# SCH006.net
KiCad netlist of a schematic drawn in Altium Designer
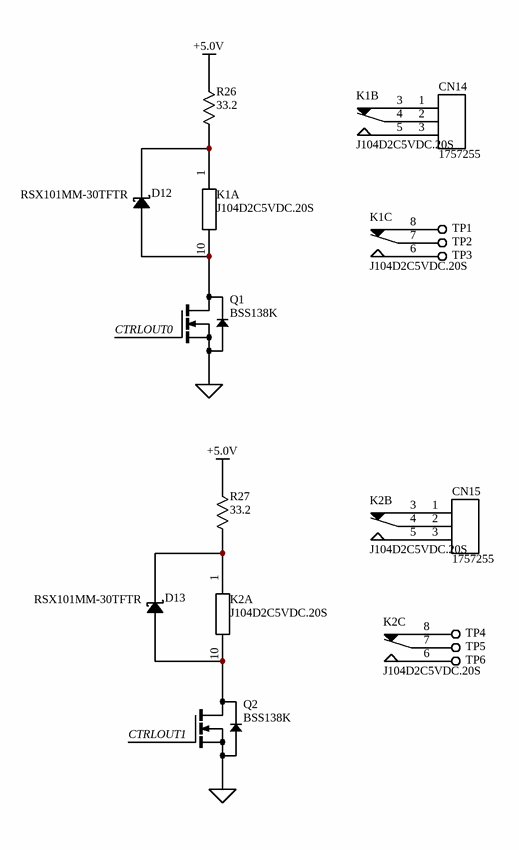
[diagram p0: SCH006.SchDoc]

(export (version "E")
  (design (tool "Eeschema 10.0.6"))
  (components
    (comp (ref "CN14")
      (value "1757255")
      (footprint "PHOENIX_1757255")
      (description "MSTBA 2,5/3-G-5,08 Pluggable Terminal Block 3 Pos 5.08mm pitch Through Hole Header")
      (fields (field (name "MANUFACTURER") "Phoenix Contact"))
      (libsource (lib "EM411-202401-RMC001-001") (part "1757255"))
    )
    (comp (ref "CN15")
      (value "1757255")
      (footprint "PHOENIX_1757255")
      (description "MSTBA 2,5/3-G-5,08 Pluggable Terminal Block 3 Pos 5.08mm pitch Through Hole Header")
      (fields (field (name "MANUFACTURER") "Phoenix Contact"))
      (libsource (lib "EM411-202401-RMC001-001") (part "1757255"))
    )
    (comp (ref "D12")
      (value "RSX101MM-30TFTR")
      (footprint "SODFL350X90-2N")
      (description "Schottky Barrier Diode")
      (fields (field (name "MANUFACTURER") "Rohm Semiconductor"))
      (libsource (lib "EM411-202401-RMC001-001") (part "RSX101MM-30TFTR"))
    )
    (comp (ref "D13")
      (value "RSX101MM-30TFTR")
      (footprint "SODFL350X90-2N")
      (description "Schottky Barrier Diode")
      (fields (field (name "MANUFACTURER") "Rohm Semiconductor"))
      (libsource (lib "EM411-202401-RMC001-001") (part "RSX101MM-30TFTR"))
    )
    (comp (ref "K1")
      (value "J104D2C5VDC.20S")
      (footprint "CIT_J104D")
      (description "J104D Series Dual Form C 5V, 2A PCB Relay")
      (fields (field (name "MANUFACTURER") "Circuit Interrupter Technology"))
      (libsource (lib "") (part "J104D2C5VDC.20S_1"))
    )
    (comp (ref "K2")
      (value "J104D2C5VDC.20S")
      (footprint "CIT_J104D")
      (description "J104D Series Dual Form C 5V, 2A PCB Relay")
      (fields (field (name "MANUFACTURER") "Circuit Interrupter Technology"))
      (libsource (lib "") (part "J104D2C5VDC.20S_1"))
    )
    (comp (ref "Q1")
      (value "BSS138K")
      (footprint "SOT95P237X111-3N")
      (description "N-Channel Logic Level Enhancement Mode Field Effect Transistor")
      (fields (field (name "MANUFACTURER") "Onsemi"))
      (libsource (lib "EM411-202401-RMC001-000-20240213-T10") (part "BSS138K"))
    )
    (comp (ref "Q2")
      (value "BSS138K")
      (footprint "SOT95P237X111-3N")
      (description "N-Channel Logic Level Enhancement Mode Field Effect Transistor")
      (fields (field (name "MANUFACTURER") "Onsemi"))
      (libsource (lib "EM411-202401-RMC001-000-20240213-T10") (part "BSS138K"))
    )
    (comp (ref "R26")
      (value "33.2")
      (footprint "RESC2012X06N")
      (description "33.2, 1%, 0.125W Thick Film Chip Resistor")
      (fields (field (name "MANUFACTURER") "Bourns") (field (name "PARTNUMBER") "CR0805-FX-33R2ELF"))
      (libsource (lib "EM411-202401-RMC001-001") (part "CR0805-FX-33R2ELF"))
    )
    (comp (ref "R27")
      (value "33.2")
      (footprint "RESC2012X06N")
      (description "33.2, 1%, 0.125W Thick Film Chip Resistor")
      (fields (field (name "MANUFACTURER") "Bourns") (field (name "PARTNUMBER") "CR0805-FX-33R2ELF"))
      (libsource (lib "EM411-202401-RMC001-001") (part "CR0805-FX-33R2ELF"))
    )
    (comp (ref "TP1")
      (value "Test Point")
      (footprint "TP100")
      (description "Test Point, Surface Mount, 3 mm")
      (fields (field (name "MANUFACTURER") "Confederation College"))
      (libsource (lib "EM411-202401-RMC001-001") (part "TP3"))
    )
    (comp (ref "TP2")
      (value "Test Point")
      (footprint "TP100")
      (description "Test Point, Surface Mount, 3 mm")
      (fields (field (name "MANUFACTURER") "Confederation College"))
      (libsource (lib "EM411-202401-RMC001-001") (part "TP3"))
    )
    (comp (ref "TP3")
      (value "Test Point")
      (footprint "TP100")
      (description "Test Point, Surface Mount, 3 mm")
      (fields (field (name "MANUFACTURER") "Confederation College"))
      (libsource (lib "EM411-202401-RMC001-001") (part "TP3"))
    )
    (comp (ref "TP4")
      (value "Test Point")
      (footprint "TP100")
      (description "Test Point, Surface Mount, 3 mm")
      (fields (field (name "MANUFACTURER") "Confederation College"))
      (libsource (lib "EM411-202401-RMC001-001") (part "TP3"))
    )
    (comp (ref "TP5")
      (value "Test Point")
      (footprint "TP100")
      (description "Test Point, Surface Mount, 3 mm")
      (fields (field (name "MANUFACTURER") "Confederation College"))
      (libsource (lib "EM411-202401-RMC001-001") (part "TP3"))
    )
    (comp (ref "TP6")
      (value "Test Point")
      (footprint "TP100")
      (description "Test Point, Surface Mount, 3 mm")
      (fields (field (name "MANUFACTURER") "Confederation College"))
      (libsource (lib "EM411-202401-RMC001-001") (part "TP3"))
    )
  )
  (nets
    (net (code "1") (name "+5.0V") (class "Default")
      (node (ref "R26") (pin "2") (pinfunction "2_2") (pintype "passive"))
      (node (ref "R27") (pin "2") (pinfunction "2_2") (pintype "passive"))
    )
    (net (code "2") (name "/CTRLOUT0") (class "Default")
      (node (ref "Q1") (pin "1") (pinfunction "G_1") (pintype "passive"))
    )
    (net (code "3") (name "/CTRLOUT1") (class "Default")
      (node (ref "Q2") (pin "1") (pinfunction "G_1") (pintype "passive"))
    )
    (net (code "4") (name "GND") (class "Default")
      (node (ref "Q1") (pin "2") (pinfunction "S_2") (pintype "passive"))
      (node (ref "Q2") (pin "2") (pinfunction "S_2") (pintype "passive"))
    )
    (net (code "5") (name "Net-(CN14-Pad1)") (class "Default")
      (node (ref "CN14") (pin "1") (pinfunction "1_1") (pintype "passive"))
      (node (ref "K1") (pin "3") (pinfunction "3_3") (pintype "passive"))
    )
    (net (code "6") (name "Net-(CN14-Pad2)") (class "Default")
      (node (ref "CN14") (pin "2") (pinfunction "2_2") (pintype "passive"))
      (node (ref "K1") (pin "4") (pinfunction "4_4") (pintype "passive"))
    )
    (net (code "7") (name "Net-(CN14-Pad3)") (class "Default")
      (node (ref "CN14") (pin "3") (pinfunction "3_3") (pintype "passive"))
      (node (ref "K1") (pin "5") (pinfunction "5_5") (pintype "passive"))
    )
    (net (code "8") (name "Net-(CN15-Pad1)") (class "Default")
      (node (ref "CN15") (pin "1") (pinfunction "1_1") (pintype "passive"))
      (node (ref "K2") (pin "3") (pinfunction "3_3") (pintype "passive"))
    )
    (net (code "9") (name "Net-(CN15-Pad2)") (class "Default")
      (node (ref "CN15") (pin "2") (pinfunction "2_2") (pintype "passive"))
      (node (ref "K2") (pin "4") (pinfunction "4_4") (pintype "passive"))
    )
    (net (code "10") (name "Net-(CN15-Pad3)") (class "Default")
      (node (ref "CN15") (pin "3") (pinfunction "3_3") (pintype "passive"))
      (node (ref "K2") (pin "5") (pinfunction "5_5") (pintype "passive"))
    )
    (net (code "11") (name "Net-(D12-PadK)") (class "Default")
      (node (ref "D12") (pin "K") (pinfunction "K_K") (pintype "passive"))
      (node (ref "K1") (pin "1") (pinfunction "1_1") (pintype "passive"))
      (node (ref "R26") (pin "1") (pinfunction "1_1") (pintype "passive"))
    )
    (net (code "12") (name "Net-(D13-PadK)") (class "Default")
      (node (ref "D13") (pin "K") (pinfunction "K_K") (pintype "passive"))
      (node (ref "K2") (pin "1") (pinfunction "1_1") (pintype "passive"))
      (node (ref "R27") (pin "1") (pinfunction "1_1") (pintype "passive"))
    )
    (net (code "13") (name "Net-(K1-Pad6)") (class "Default")
      (node (ref "K1") (pin "6") (pinfunction "6_6") (pintype "passive"))
      (node (ref "TP3") (pin "1") (pinfunction "1_1") (pintype "passive"))
    )
    (net (code "14") (name "Net-(K1-Pad7)") (class "Default")
      (node (ref "K1") (pin "7") (pinfunction "7_7") (pintype "passive"))
      (node (ref "TP2") (pin "1") (pinfunction "1_1") (pintype "passive"))
    )
    (net (code "15") (name "Net-(K1-Pad8)") (class "Default")
      (node (ref "K1") (pin "8") (pinfunction "8_8") (pintype "passive"))
      (node (ref "TP1") (pin "1") (pinfunction "1_1") (pintype "passive"))
    )
    (net (code "16") (name "Net-(K2-Pad6)") (class "Default")
      (node (ref "K2") (pin "6") (pinfunction "6_6") (pintype "passive"))
      (node (ref "TP6") (pin "1") (pinfunction "1_1") (pintype "passive"))
    )
    (net (code "17") (name "Net-(K2-Pad7)") (class "Default")
      (node (ref "K2") (pin "7") (pinfunction "7_7") (pintype "passive"))
      (node (ref "TP5") (pin "1") (pinfunction "1_1") (pintype "passive"))
    )
    (net (code "18") (name "Net-(K2-Pad8)") (class "Default")
      (node (ref "K2") (pin "8") (pinfunction "8_8") (pintype "passive"))
      (node (ref "TP4") (pin "1") (pinfunction "1_1") (pintype "passive"))
    )
    (net (code "19") (name "Net-(Q1-D)") (class "Default")
      (node (ref "D12") (pin "A") (pinfunction "A_A") (pintype "passive"))
      (node (ref "K1") (pin "10") (pinfunction "10_10") (pintype "passive"))
      (node (ref "Q1") (pin "3") (pinfunction "D_3") (pintype "passive"))
    )
    (net (code "20") (name "Net-(Q2-D)") (class "Default")
      (node (ref "D13") (pin "A") (pinfunction "A_A") (pintype "passive"))
      (node (ref "K2") (pin "10") (pinfunction "10_10") (pintype "passive"))
      (node (ref "Q2") (pin "3") (pinfunction "D_3") (pintype "passive"))
    )
  )
)
